# MatchX_SoM24.net
KiCad netlist of a schematic drawn in Altium Designer
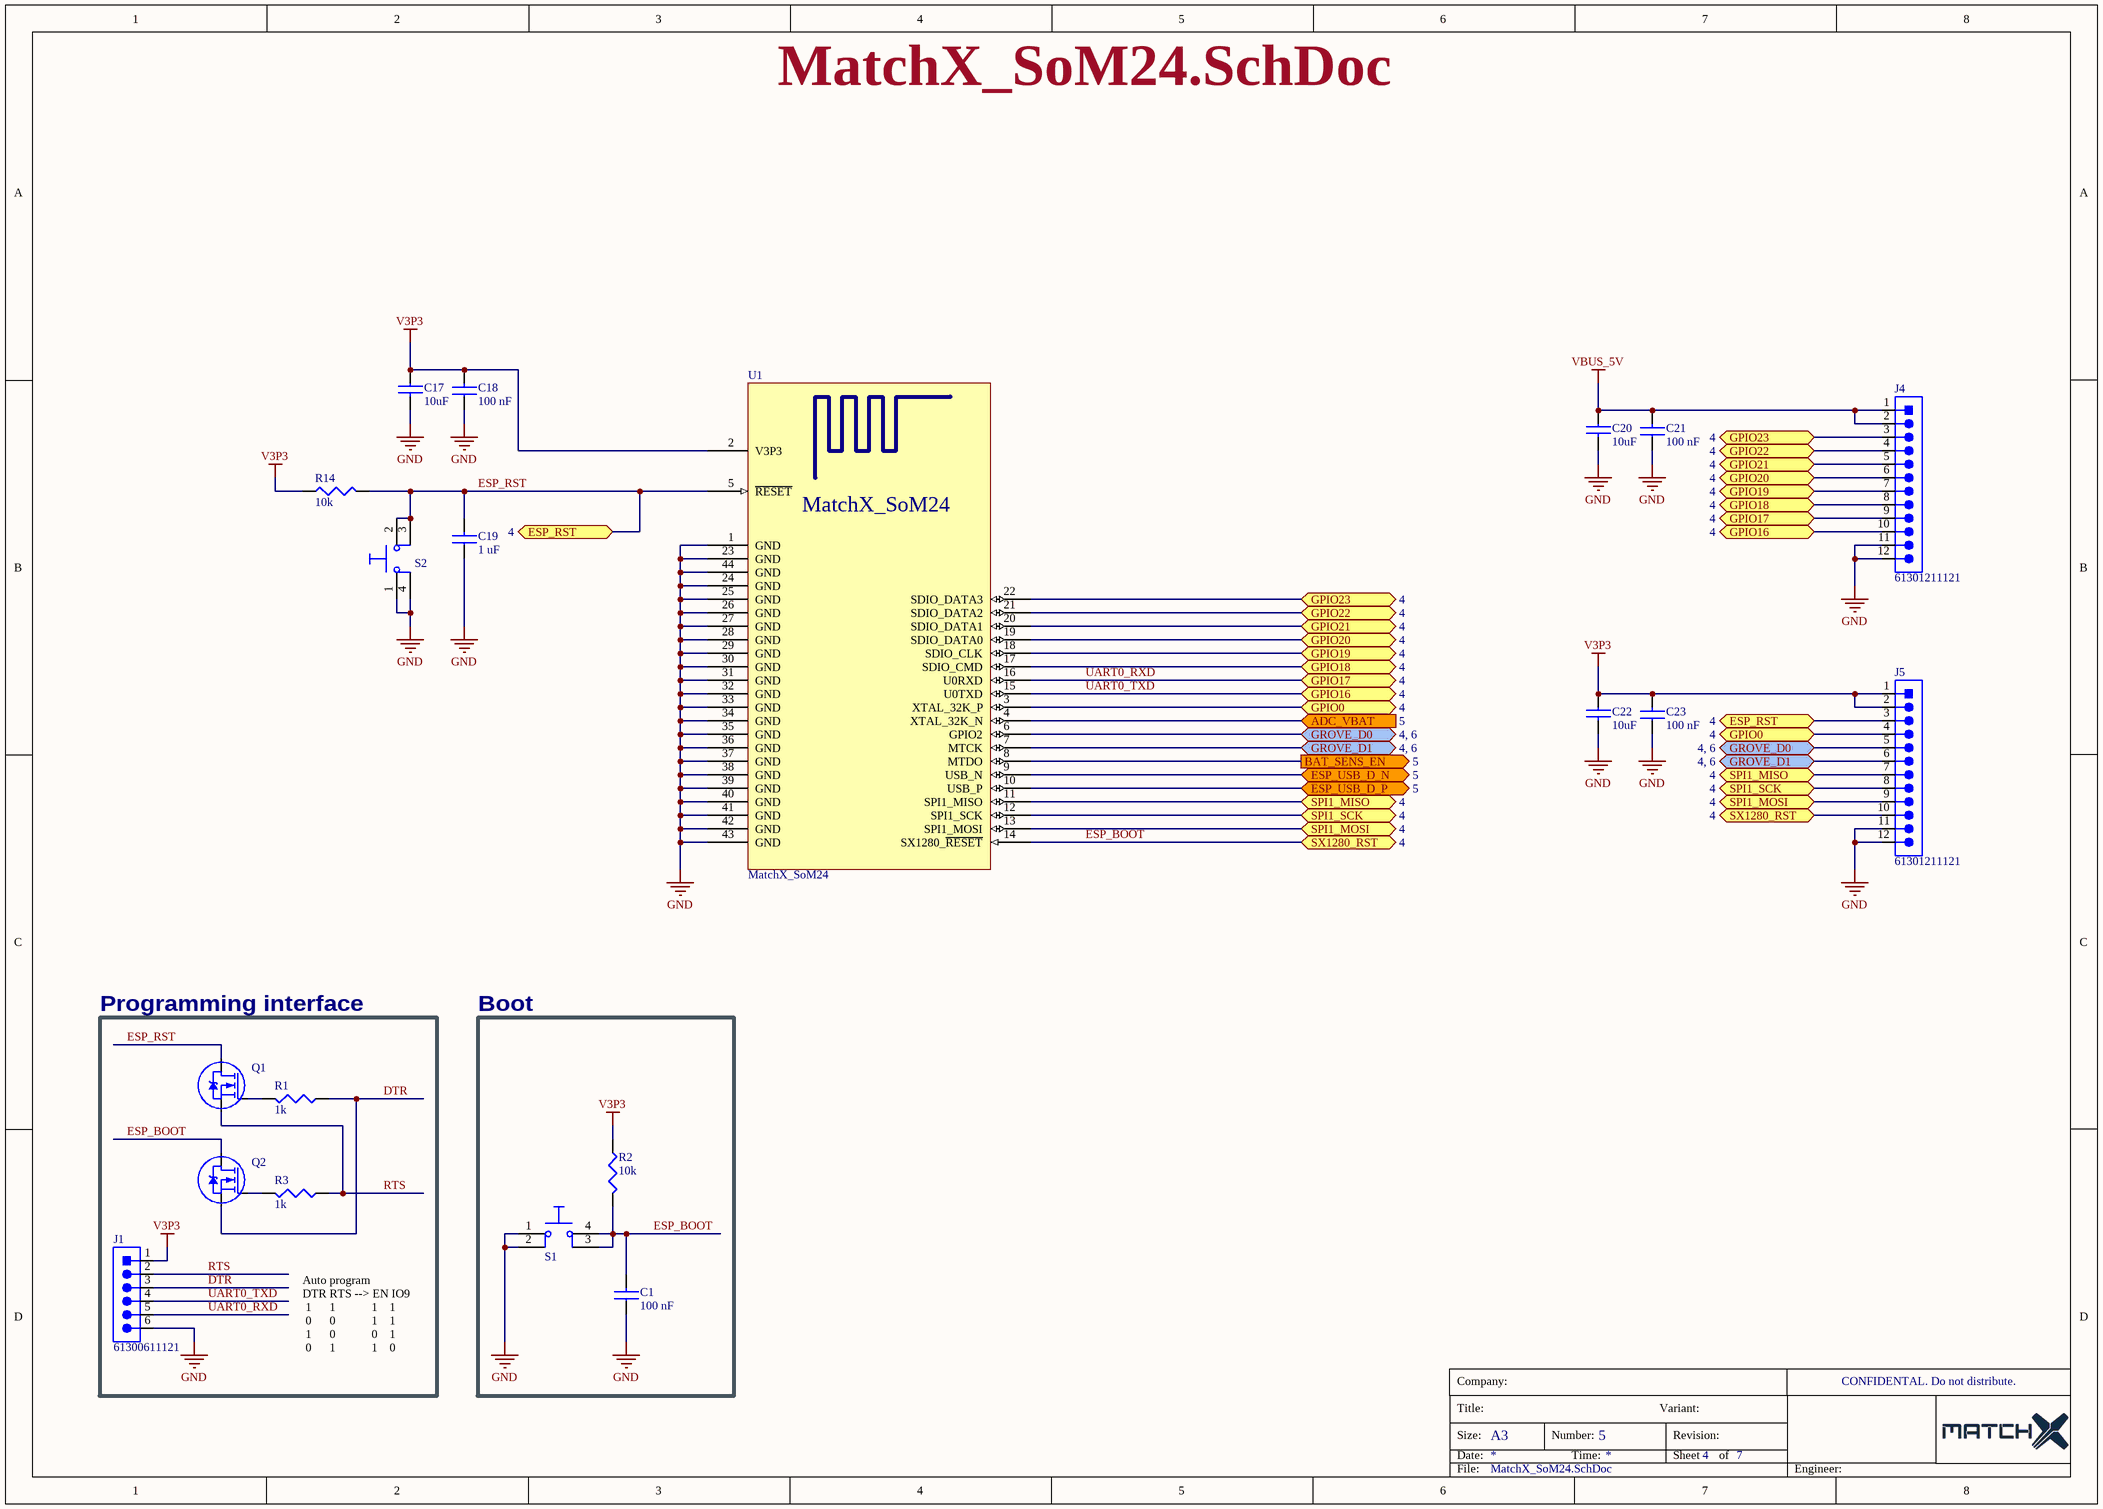
[diagram p0: MatchX_SoM24.SchDoc]

(export (version "E")
  (design (tool "Eeschema 10.0.6"))
  (components
    (comp (ref "C1")
      (value "100 nF")
      (footprint "C0603")
      (description "CAP, CERM, 100 nF, 50V, +/- 10%, X7R, 0603")
      (fields (field (name "TOLERANCE") "10%"))
      (libsource (lib "psblib") (part "C0603-100nF_50V"))
    )
    (comp (ref "C17")
      (value "10uF")
      (footprint "C0805")
      (description "CAP, CERM, 10uF, 16V, +/- 20%, X5R, 0805")
      (fields (field (name "TOLERANCE") "20%"))
      (libsource (lib "psblib") (part "C0805-10uF_16V"))
    )
    (comp (ref "C18")
      (value "100 nF")
      (footprint "C0603")
      (description "CAP, CERM, 100 nF, 50V, +/- 10%, X7R, 0603")
      (fields (field (name "TOLERANCE") "10%"))
      (libsource (lib "psblib") (part "C0603-100nF_50V"))
    )
    (comp (ref "C19")
      (value "1 uF")
      (footprint "C0603")
      (description "CAP, CERM, 1 uF, 25 V, +/- 10%, X7R, 0603")
      (fields (field (name "TOLERANCE") "10%"))
      (libsource (lib "psblib") (part "C0603-1uF_25V"))
    )
    (comp (ref "C20")
      (value "10uF")
      (footprint "C0805")
      (description "CAP, CERM, 10uF, 16V, +/- 20%, X5R, 0805")
      (fields (field (name "TOLERANCE") "20%"))
      (libsource (lib "psblib") (part "C0805-10uF_16V"))
    )
    (comp (ref "C21")
      (value "100 nF")
      (footprint "C0603")
      (description "CAP, CERM, 100 nF, 50V, +/- 10%, X7R, 0603")
      (fields (field (name "TOLERANCE") "10%"))
      (libsource (lib "psblib") (part "C0603-100nF_50V"))
    )
    (comp (ref "C22")
      (value "10uF")
      (footprint "C0805")
      (description "CAP, CERM, 10uF, 16V, +/- 20%, X5R, 0805")
      (fields (field (name "TOLERANCE") "20%"))
      (libsource (lib "psblib") (part "C0805-10uF_16V"))
    )
    (comp (ref "C23")
      (value "100 nF")
      (footprint "C0603")
      (description "CAP, CERM, 100 nF, 50V, +/- 10%, X7R, 0603")
      (fields (field (name "TOLERANCE") "10%"))
      (libsource (lib "psblib") (part "C0603-100nF_50V"))
    )
    (comp (ref "J1")
      (value "61300611121")
      (footprint "WURTH_61300611121")
      (description "Header, 2.54 mm, 6x1, Gold, TH")
      (fields (field (name "MANUFACTURER") "Wurth Electronics"))
      (libsource (lib "psblib") (part "CON_61300611121"))
    )
    (comp (ref "J4")
      (value "61301211121")
      (footprint "WURTH_61301211121")
      (description "Header, 2.54 mm, 12x1, Gold, TH")
      (fields (field (name "MANUFACTURER") "Wurth Electronics"))
      (libsource (lib "psblib") (part "CON_61301211121"))
    )
    (comp (ref "J5")
      (value "61301211121")
      (footprint "WURTH_61301211121")
      (description "Header, 2.54 mm, 12x1, Gold, TH")
      (fields (field (name "MANUFACTURER") "Wurth Electronics"))
      (libsource (lib "psblib") (part "CON_61301211121"))
    )
    (comp (ref "Q1")
      (value "DMN3023L-7")
      (footprint "SOT-23")
      (description "MOSFETN-CH 30V 6.2A SOT23-3")
      (fields
        (field (name "MANUFACTURER") "Diodes")
        (field (name ".CHECKED PCB") "OK M")
        (field (name ".CHECKED SCH") "OK M")
      )
      (libsource (lib "psblib") (part "NMOSFET_DMN3023L-7"))
    )
    (comp (ref "Q2")
      (value "DMN3023L-7")
      (footprint "SOT-23")
      (description "MOSFETN-CH 30V 6.2A SOT23-3")
      (fields
        (field (name "MANUFACTURER") "Diodes")
        (field (name ".CHECKED PCB") "OK M")
        (field (name ".CHECKED SCH") "OK M")
      )
      (libsource (lib "psblib") (part "NMOSFET_DMN3023L-7"))
    )
    (comp (ref "R1")
      (value "1k")
      (footprint "R0603")
      (description "RES, 1k, 1%, 0.063 W, 0603")
      (fields
        (field (name "TOLERANCE") "±1%")
        (field (name ".CHECKED PCB") "OK RF")
        (field (name ".CHECKED SCH") "RF")
      )
      (libsource (lib "psblib") (part "R0603-1k"))
    )
    (comp (ref "R2")
      (value "10k")
      (footprint "R0402")
      (description "RES, 10k, 1%, 1/16 W, 0402")
      (fields
        (field (name "TOLERANCE") "±1%")
        (field (name ".CHECKED PCB") "OK RF")
        (field (name ".CHECKED SCH") "RF")
      )
      (libsource (lib "psblib") (part "R0402-10k"))
    )
    (comp (ref "R3")
      (value "1k")
      (footprint "R0603")
      (description "RES, 1k, 1%, 0.063 W, 0603")
      (fields
        (field (name "TOLERANCE") "±1%")
        (field (name ".CHECKED PCB") "OK RF")
        (field (name ".CHECKED SCH") "RF")
      )
      (libsource (lib "psblib") (part "R0603-1k"))
    )
    (comp (ref "R14")
      (value "10k")
      (footprint "R0402")
      (description "RES, 10k, 1%, 1/16 W, 0402")
      (fields
        (field (name "TOLERANCE") "±1%")
        (field (name ".CHECKED PCB") "OK RF")
        (field (name ".CHECKED SCH") "RF")
      )
      (libsource (lib "psblib") (part "R0402-10k"))
    )
    (comp (ref "S1")
      (value "TS-1108A")
      (footprint "TS-1108A")
      (description "Switch Tactile N.O. SPST Button 12VDC 50mA 5N SMD T/R")
      (fields (field (name "MANUFACTURER") "ROPARTS"))
      (libsource (lib "psblib") (part "TS-1108A"))
    )
    (comp (ref "S2")
      (value "TS-1108A")
      (footprint "TS-1108A")
      (description "Switch Tactile N.O. SPST Button 12VDC 50mA 5N SMD T/R")
      (fields (field (name "MANUFACTURER") "ROPARTS"))
      (libsource (lib "") (part "TS-1108A_1"))
    )
    (comp (ref "U1")
      (value "MatchX_SoM24")
      (footprint "MatchX_SoM24")
      (description "MatchX_SoM24 LoRa, Wi-Fi 6 + Bluetooth 5 (LE)")
      (fields (field (name "MANUFACTURER") "MatchX"))
      (libsource (lib "psblib") (part "MatchX_SoM24"))
    )
  )
  (nets
    (net (code "1") (name "/ADC_VBAT") (class "Default")
      (node (ref "U1") (pin "4") (pinfunction "XTAL_32K_N_4") (pintype "bidirectional"))
    )
    (net (code "2") (name "/BAT_SENS_EN") (class "Default")
      (node (ref "U1") (pin "8") (pinfunction "MTDO_8") (pintype "bidirectional"))
    )
    (net (code "3") (name "/DTR") (class "Default")
      (node (ref "J1") (pin "3") (pinfunction "3_3") (pintype "passive"))
      (node (ref "Q2") (pin "2") (pinfunction "S_2") (pintype "passive"))
      (node (ref "R1") (pin "2") (pinfunction "2_2") (pintype "passive"))
    )
    (net (code "4") (name "/ESP_BOOT") (class "Default")
      (node (ref "C1") (pin "2") (pinfunction "2_2") (pintype "passive"))
      (node (ref "J5") (pin "10") (pinfunction "10_10") (pintype "passive"))
      (node (ref "Q2") (pin "3") (pinfunction "D_3") (pintype "passive"))
      (node (ref "R2") (pin "2") (pinfunction "2_2") (pintype "passive"))
      (node (ref "S1") (pin "3") (pinfunction "3_3") (pintype "passive"))
      (node (ref "S1") (pin "4") (pinfunction "4_4") (pintype "passive"))
      (node (ref "U1") (pin "14") (pinfunction "SX1280_~{RESET}_14") (pintype "input"))
    )
    (net (code "5") (name "/ESP_RST") (class "Default")
      (node (ref "C19") (pin "2") (pinfunction "2_2") (pintype "passive"))
      (node (ref "J5") (pin "3") (pinfunction "3_3") (pintype "passive"))
      (node (ref "Q1") (pin "3") (pinfunction "D_3") (pintype "passive"))
      (node (ref "R14") (pin "2") (pinfunction "2_2") (pintype "passive"))
      (node (ref "S2") (pin "2") (pinfunction "2_2") (pintype "passive"))
      (node (ref "S2") (pin "3") (pinfunction "3_3") (pintype "passive"))
      (node (ref "U1") (pin "5") (pinfunction "~{RESET}_5") (pintype "input"))
    )
    (net (code "6") (name "/ESP_USB_D_N") (class "Default")
      (node (ref "U1") (pin "9") (pinfunction "USB_N_9") (pintype "bidirectional"))
    )
    (net (code "7") (name "/ESP_USB_D_P") (class "Default")
      (node (ref "U1") (pin "10") (pinfunction "USB_P_10") (pintype "bidirectional"))
    )
    (net (code "8") (name "/GPIO0") (class "Default")
      (node (ref "J5") (pin "4") (pinfunction "4_4") (pintype "passive"))
      (node (ref "U1") (pin "3") (pinfunction "XTAL_32K_P_3") (pintype "bidirectional"))
    )
    (net (code "9") (name "/GPIO18") (class "Default")
      (node (ref "J4") (pin "8") (pinfunction "8_8") (pintype "passive"))
      (node (ref "U1") (pin "17") (pinfunction "SDIO_CMD_17") (pintype "bidirectional"))
    )
    (net (code "10") (name "/GPIO19") (class "Default")
      (node (ref "J4") (pin "7") (pinfunction "7_7") (pintype "passive"))
      (node (ref "U1") (pin "18") (pinfunction "SDIO_CLK_18") (pintype "bidirectional"))
    )
    (net (code "11") (name "/GPIO20") (class "Default")
      (node (ref "J4") (pin "6") (pinfunction "6_6") (pintype "passive"))
      (node (ref "U1") (pin "19") (pinfunction "SDIO_DATA0_19") (pintype "bidirectional"))
    )
    (net (code "12") (name "/GPIO21") (class "Default")
      (node (ref "J4") (pin "5") (pinfunction "5_5") (pintype "passive"))
      (node (ref "U1") (pin "20") (pinfunction "SDIO_DATA1_20") (pintype "bidirectional"))
    )
    (net (code "13") (name "/GPIO22") (class "Default")
      (node (ref "J4") (pin "4") (pinfunction "4_4") (pintype "passive"))
      (node (ref "U1") (pin "21") (pinfunction "SDIO_DATA2_21") (pintype "bidirectional"))
    )
    (net (code "14") (name "/GPIO23") (class "Default")
      (node (ref "J4") (pin "3") (pinfunction "3_3") (pintype "passive"))
      (node (ref "U1") (pin "22") (pinfunction "SDIO_DATA3_22") (pintype "bidirectional"))
    )
    (net (code "15") (name "/GROVE_D0") (class "Default")
      (node (ref "J5") (pin "5") (pinfunction "5_5") (pintype "passive"))
      (node (ref "U1") (pin "6") (pinfunction "GPIO2_6") (pintype "bidirectional"))
    )
    (net (code "16") (name "/GROVE_D1") (class "Default")
      (node (ref "J5") (pin "6") (pinfunction "6_6") (pintype "passive"))
      (node (ref "U1") (pin "7") (pinfunction "MTCK_7") (pintype "bidirectional"))
    )
    (net (code "17") (name "/RTS") (class "Default")
      (node (ref "J1") (pin "2") (pinfunction "2_2") (pintype "passive"))
      (node (ref "Q1") (pin "2") (pinfunction "S_2") (pintype "passive"))
      (node (ref "R3") (pin "2") (pinfunction "2_2") (pintype "passive"))
    )
    (net (code "18") (name "/SPI1_MISO") (class "Default")
      (node (ref "J5") (pin "7") (pinfunction "7_7") (pintype "passive"))
      (node (ref "U1") (pin "11") (pinfunction "SPI1_MISO_11") (pintype "bidirectional"))
    )
    (net (code "19") (name "/SPI1_MOSI") (class "Default")
      (node (ref "J5") (pin "9") (pinfunction "9_9") (pintype "passive"))
      (node (ref "U1") (pin "13") (pinfunction "SPI1_MOSI_13") (pintype "bidirectional"))
    )
    (net (code "20") (name "/SPI1_SCK") (class "Default")
      (node (ref "J5") (pin "8") (pinfunction "8_8") (pintype "passive"))
      (node (ref "U1") (pin "12") (pinfunction "SPI1_SCK_12") (pintype "bidirectional"))
    )
    (net (code "21") (name "/UART0_RXD") (class "Default")
      (node (ref "J1") (pin "5") (pinfunction "5_5") (pintype "passive"))
      (node (ref "J4") (pin "9") (pinfunction "9_9") (pintype "passive"))
      (node (ref "U1") (pin "16") (pinfunction "U0RXD_16") (pintype "bidirectional"))
    )
    (net (code "22") (name "/UART0_TXD") (class "Default")
      (node (ref "J1") (pin "4") (pinfunction "4_4") (pintype "passive"))
      (node (ref "J4") (pin "10") (pinfunction "10_10") (pintype "passive"))
      (node (ref "U1") (pin "15") (pinfunction "U0TXD_15") (pintype "bidirectional"))
    )
    (net (code "23") (name "GND") (class "Default")
      (node (ref "C1") (pin "1") (pinfunction "1_1") (pintype "passive"))
      (node (ref "C17") (pin "2") (pinfunction "2_2") (pintype "passive"))
      (node (ref "C18") (pin "1") (pinfunction "1_1") (pintype "passive"))
      (node (ref "C19") (pin "1") (pinfunction "1_1") (pintype "passive"))
      (node (ref "C20") (pin "2") (pinfunction "2_2") (pintype "passive"))
      (node (ref "C21") (pin "1") (pinfunction "1_1") (pintype "passive"))
      (node (ref "C22") (pin "2") (pinfunction "2_2") (pintype "passive"))
      (node (ref "C23") (pin "1") (pinfunction "1_1") (pintype "passive"))
      (node (ref "J1") (pin "6") (pinfunction "6_6") (pintype "passive"))
      (node (ref "J4") (pin "11") (pinfunction "11_11") (pintype "passive"))
      (node (ref "J4") (pin "12") (pinfunction "12_12") (pintype "passive"))
      (node (ref "J5") (pin "11") (pinfunction "11_11") (pintype "passive"))
      (node (ref "J5") (pin "12") (pinfunction "12_12") (pintype "passive"))
      (node (ref "S1") (pin "1") (pinfunction "1_1") (pintype "passive"))
      (node (ref "S1") (pin "2") (pinfunction "2_2") (pintype "passive"))
      (node (ref "S2") (pin "1") (pinfunction "1_1") (pintype "passive"))
      (node (ref "S2") (pin "4") (pinfunction "4_4") (pintype "passive"))
      (node (ref "U1") (pin "1") (pinfunction "GND_1") (pintype "passive"))
      (node (ref "U1") (pin "23") (pinfunction "GND_23") (pintype "passive"))
      (node (ref "U1") (pin "24") (pinfunction "GND_24") (pintype "passive"))
      (node (ref "U1") (pin "25") (pinfunction "GND_25") (pintype "passive"))
      (node (ref "U1") (pin "26") (pinfunction "GND_26") (pintype "passive"))
      (node (ref "U1") (pin "27") (pinfunction "GND_27") (pintype "passive"))
      (node (ref "U1") (pin "28") (pinfunction "GND_28") (pintype "passive"))
      (node (ref "U1") (pin "29") (pinfunction "GND_29") (pintype "passive"))
      (node (ref "U1") (pin "30") (pinfunction "GND_30") (pintype "passive"))
      (node (ref "U1") (pin "31") (pinfunction "GND_31") (pintype "passive"))
      (node (ref "U1") (pin "32") (pinfunction "GND_32") (pintype "passive"))
      (node (ref "U1") (pin "33") (pinfunction "GND_33") (pintype "passive"))
      (node (ref "U1") (pin "34") (pinfunction "GND_34") (pintype "passive"))
      (node (ref "U1") (pin "35") (pinfunction "GND_35") (pintype "passive"))
      (node (ref "U1") (pin "36") (pinfunction "GND_36") (pintype "passive"))
      (node (ref "U1") (pin "37") (pinfunction "GND_37") (pintype "passive"))
      (node (ref "U1") (pin "38") (pinfunction "GND_38") (pintype "passive"))
      (node (ref "U1") (pin "39") (pinfunction "GND_39") (pintype "passive"))
      (node (ref "U1") (pin "40") (pinfunction "GND_40") (pintype "passive"))
      (node (ref "U1") (pin "41") (pinfunction "GND_41") (pintype "passive"))
      (node (ref "U1") (pin "42") (pinfunction "GND_42") (pintype "passive"))
      (node (ref "U1") (pin "43") (pinfunction "GND_43") (pintype "passive"))
      (node (ref "U1") (pin "44") (pinfunction "GND_44") (pintype "passive"))
    )
    (net (code "24") (name "Net-(Q1-G)") (class "Default")
      (node (ref "Q1") (pin "1") (pinfunction "G_1") (pintype "passive"))
      (node (ref "R1") (pin "1") (pinfunction "1_1") (pintype "passive"))
    )
    (net (code "25") (name "Net-(Q2-G)") (class "Default")
      (node (ref "Q2") (pin "1") (pinfunction "G_1") (pintype "passive"))
      (node (ref "R3") (pin "1") (pinfunction "1_1") (pintype "passive"))
    )
    (net (code "26") (name "V3P3") (class "Default")
      (node (ref "C17") (pin "1") (pinfunction "1_1") (pintype "passive"))
      (node (ref "C18") (pin "2") (pinfunction "2_2") (pintype "passive"))
      (node (ref "C22") (pin "1") (pinfunction "1_1") (pintype "passive"))
      (node (ref "C23") (pin "2") (pinfunction "2_2") (pintype "passive"))
      (node (ref "J1") (pin "1") (pinfunction "1_1") (pintype "passive"))
      (node (ref "J5") (pin "1") (pinfunction "1_1") (pintype "passive"))
      (node (ref "J5") (pin "2") (pinfunction "2_2") (pintype "passive"))
      (node (ref "R14") (pin "1") (pinfunction "1_1") (pintype "passive"))
      (node (ref "R2") (pin "1") (pinfunction "1_1") (pintype "passive"))
      (node (ref "U1") (pin "2") (pinfunction "V3P3_2") (pintype "power_in"))
    )
    (net (code "27") (name "VBUS_5V") (class "Default")
      (node (ref "C20") (pin "1") (pinfunction "1_1") (pintype "passive"))
      (node (ref "C21") (pin "2") (pinfunction "2_2") (pintype "passive"))
      (node (ref "J4") (pin "1") (pinfunction "1_1") (pintype "passive"))
      (node (ref "J4") (pin "2") (pinfunction "2_2") (pintype "passive"))
    )
  )
)
